# Receiver_VLC.net
KiCad netlist of a schematic drawn in Altium Designer
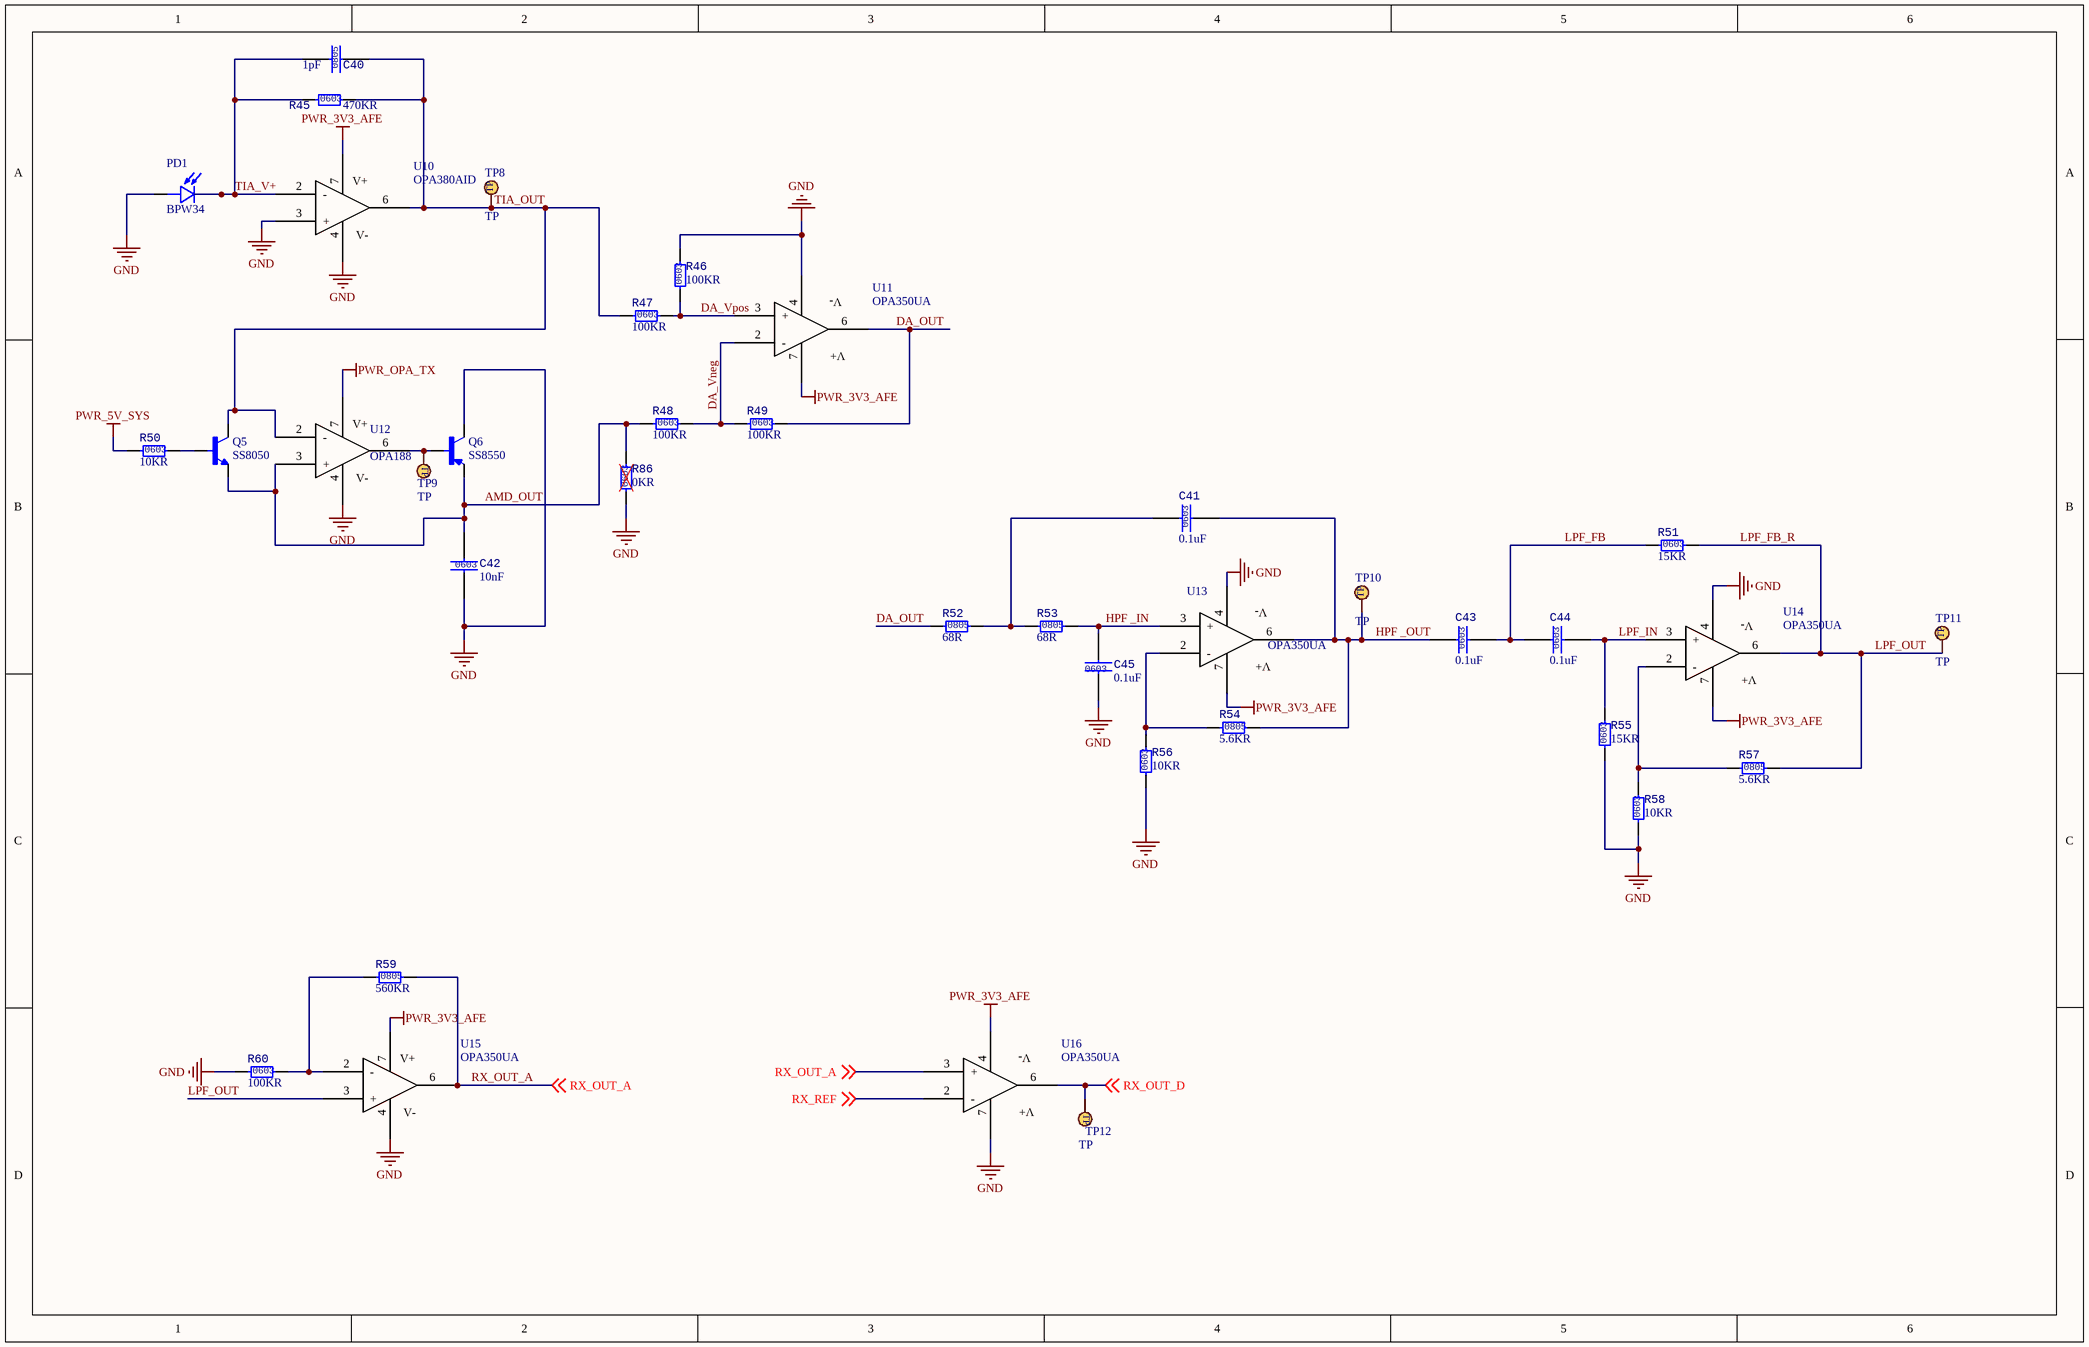
[diagram p0: Receiver_VLC.SchDoc]

(export (version "E")
  (design (tool "Eeschema 10.0.6"))
  (components
    (comp (ref "C40")
      (value "1pF")
      (footprint "CAPCER 0805 SMD")
      (fields (field (name "SIZE") "0805"))
      (libsource (lib "Database_Libs2") (part "CAPACITOR"))
    )
    (comp (ref "C41")
      (value "0.1uF")
      (footprint "CAPCER 0805 SMD")
      (description "CAPACITOR SMD 0.1uF 50V 10% 0603")
      (fields (field (name "SIZE") "0603") (field (name "TOLERANCE") "10%"))
      (libsource (lib "Database_Libs1") (part "CAPACITOR"))
    )
    (comp (ref "C42")
      (value "10nF")
      (footprint "CAPCER 0805 SMD")
      (description "CAPACITOR SMD 0.01uF 50V 10% 0603")
      (fields
        (field (name "SIZE") "0603")
        (field (name "TOLERANCE") "10%")
        (field (name "Comment") "Tụ Gốm 0603 10nF 50V")
      )
      (libsource (lib "Database_Libs1") (part "CAPACITOR"))
    )
    (comp (ref "C43")
      (value "0.1uF")
      (footprint "CAPCER 0805 SMD")
      (description "CAPACITOR SMD 0.1uF 50V 10% 0603")
      (fields (field (name "SIZE") "0603") (field (name "TOLERANCE") "10%"))
      (libsource (lib "Database_Libs1") (part "CAPACITOR"))
    )
    (comp (ref "C44")
      (value "0.1uF")
      (footprint "CAPCER 0805 SMD")
      (description "CAPACITOR SMD 0.1uF 50V 10% 0603")
      (fields (field (name "SIZE") "0603") (field (name "TOLERANCE") "10%"))
      (libsource (lib "Database_Libs1") (part "CAPACITOR"))
    )
    (comp (ref "C45")
      (value "0.1uF")
      (footprint "CAPCER 0805 SMD")
      (description "CAPACITOR SMD 0.1uF 50V 10% 0603")
      (fields (field (name "SIZE") "0603") (field (name "TOLERANCE") "10%"))
      (libsource (lib "Database_Libs1") (part "CAPACITOR"))
    )
    (comp (ref "PD1") (value "BPW34") (footprint "DIP-2") (libsource (lib "Database_Libs2") (part "PD")))
    (comp (ref "Q5")
      (value "SS8050")
      (footprint "SOT23-3")
      (description "SS8050 Y1 Transistor NPN 25V 1.5A 3 Chân SOT-23")
      (libsource (lib "Database_Libs2") (part "NPN"))
    )
    (comp (ref "Q6")
      (value "SS8550")
      (footprint "SOT23-3")
      (description "SS8550 Y2 Transistor PNP 25V 1.5A 3 Chân SOT-23")
      (libsource (lib "Database_Libs2") (part "PNP"))
    )
    (comp (ref "R45")
      (value "470KR")
      (footprint "RESC 0603(1608) SMD")
      (description "RESISTOR SMD 470KR OHM 1% 100mW 0603")
      (fields (field (name "SIZE") "0603") (field (name "TOLERANCE") "1%"))
      (libsource (lib "Database_Libs1") (part "RESISTOR"))
    )
    (comp (ref "R46")
      (value "100KR")
      (footprint "RESC 0603(1608) SMD")
      (description "RESISTOR SMD 100KR OHM 1% 100mW 0603")
      (fields (field (name "SIZE") "0603") (field (name "TOLERANCE") "1%"))
      (libsource (lib "") (part "RESISTOR_1"))
    )
    (comp (ref "R47")
      (value "100KR")
      (footprint "RESC 0603(1608) SMD")
      (description "RESISTOR SMD 100KR OHM 1% 100mW 0603")
      (fields (field (name "SIZE") "0603") (field (name "TOLERANCE") "1%"))
      (libsource (lib "Database_Libs1") (part "RESISTOR"))
    )
    (comp (ref "R48")
      (value "100KR")
      (footprint "RESC 0603(1608) SMD")
      (description "RESISTOR SMD 100KR OHM 1% 100mW 0603")
      (fields (field (name "SIZE") "0603") (field (name "TOLERANCE") "1%"))
      (libsource (lib "Database_Libs1") (part "RESISTOR"))
    )
    (comp (ref "R49")
      (value "100KR")
      (footprint "RESC 0603(1608) SMD")
      (description "RESISTOR SMD 100KR OHM 1% 100mW 0603")
      (fields (field (name "SIZE") "0603") (field (name "TOLERANCE") "1%"))
      (libsource (lib "Database_Libs1") (part "RESISTOR"))
    )
    (comp (ref "R50")
      (value "10KR")
      (footprint "RESC 0603(1608) SMD")
      (description "RESISTOR SMD 10KR OHM 1% 100mW 0603")
      (fields (field (name "SIZE") "0603") (field (name "TOLERANCE") "1%"))
      (libsource (lib "Database_Libs1") (part "RESISTOR"))
    )
    (comp (ref "R51")
      (value "15KR")
      (footprint "RESC 0603(1608) SMD")
      (fields (field (name "SIZE") "0603"))
      (libsource (lib "Database_Libs2") (part "RESISTOR"))
    )
    (comp (ref "R52")
      (value "68R")
      (footprint "RESC 0805 SMD")
      (description "Điện Trở 68 Ohm 0805 1%")
      (fields (field (name "SIZE") "0805"))
      (libsource (lib "Database_Libs2") (part "RESISTOR"))
    )
    (comp (ref "R53")
      (value "68R")
      (footprint "RESC 0805 SMD")
      (description "Điện Trở 68 Ohm 0805 1%")
      (fields (field (name "SIZE") "0805"))
      (libsource (lib "Database_Libs2") (part "RESISTOR"))
    )
    (comp (ref "R54")
      (value "5.6KR")
      (footprint "RESC 0805 SMD")
      (description "RESISTOR SMD 5.6KR OHM 1% 125mW 0805")
      (fields (field (name "SIZE") "0805") (field (name "TOLERANCE") "1%"))
      (libsource (lib "Database_Libs1") (part "RESISTOR"))
    )
    (comp (ref "R55")
      (value "15KR")
      (footprint "RESC 0603(1608) SMD")
      (fields (field (name "SIZE") "0603"))
      (libsource (lib "") (part "RESISTOR_1"))
    )
    (comp (ref "R56")
      (value "10KR")
      (footprint "RESC 0603(1608) SMD")
      (description "RESISTOR SMD 10KR OHM 1% 100mW 0603")
      (fields (field (name "SIZE") "0603") (field (name "TOLERANCE") "1%"))
      (libsource (lib "") (part "RESISTOR_1"))
    )
    (comp (ref "R57")
      (value "5.6KR")
      (footprint "RESC 0805 SMD")
      (description "RESISTOR SMD 5.6KR OHM 1% 125mW 0805")
      (fields (field (name "SIZE") "0805") (field (name "TOLERANCE") "1%"))
      (libsource (lib "Database_Libs1") (part "RESISTOR"))
    )
    (comp (ref "R58")
      (value "10KR")
      (footprint "RESC 0603(1608) SMD")
      (description "RESISTOR SMD 10KR OHM 1% 100mW 0603")
      (fields (field (name "SIZE") "0603") (field (name "TOLERANCE") "1%"))
      (libsource (lib "") (part "RESISTOR_1"))
    )
    (comp (ref "R59")
      (value "560KR")
      (footprint "RESC 0805 SMD")
      (fields (field (name "SIZE") "0805"))
      (libsource (lib "Database_Libs2") (part "RESISTOR"))
    )
    (comp (ref "R60")
      (value "100KR")
      (footprint "RESC 0603(1608) SMD")
      (description "RESISTOR SMD 100KR OHM 1% 100mW 0603")
      (fields (field (name "SIZE") "0603") (field (name "TOLERANCE") "1%"))
      (libsource (lib "Database_Libs1") (part "RESISTOR"))
    )
    (comp (ref "R86")
      (value "0KR")
      (footprint "RESC 0603(1608) SMD")
      (description "RESISTOR SMD 0KR OHM 1% 100mW 0603")
      (fields (field (name "SIZE") "0603") (field (name "TOLERANCE") "1%") (field (name "Comment") "0R-dni"))
      (libsource (lib "") (part "RESISTOR_1"))
    )
    (comp (ref "TP8")
      (value "TP")
      (footprint "TP_THT_1P0")
      (fields (field (name "Comment") "TEST POINT"))
      (libsource (lib "Database_Libs2") (part "Test_point"))
    )
    (comp (ref "TP9")
      (value "TP")
      (footprint "TP_THT_1P0")
      (fields (field (name "Comment") "TEST POINT"))
      (libsource (lib "Database_Libs2") (part "Test_point"))
    )
    (comp (ref "TP10")
      (value "TP")
      (footprint "TP_THT_1P0")
      (fields (field (name "Comment") "TEST POINT"))
      (libsource (lib "Database_Libs2") (part "Test_point"))
    )
    (comp (ref "TP11")
      (value "TP")
      (footprint "TP_THT_1P0")
      (fields (field (name "Comment") "TEST POINT"))
      (libsource (lib "Database_Libs2") (part "Test_point"))
    )
    (comp (ref "TP12")
      (value "TP")
      (footprint "TP_THT_1P0")
      (fields (field (name "Comment") "TEST POINT"))
      (libsource (lib "Database_Libs2") (part "Test_point"))
    )
    (comp (ref "U10")
      (value "OPA380AID")
      (footprint "8-SOIC-OPA")
      (libsource (lib "Database_Libs2") (part "OPA380AID"))
    )
    (comp (ref "U11")
      (value "OPA350UA")
      (footprint "8-SOIC-OPA")
      (libsource (lib "Database_Libs2") (part "OPA350UA"))
    )
    (comp (ref "U12")
      (value "OPA188")
      (footprint "8-SOIC-OPA")
      (description "Zero-Drift Amplifier 1 Circuit Rail-to-Rail 8-SOIC")
      (fields (field (name "Comment") "OPA188AID"))
      (libsource (lib "Database_Libs1") (part "OPA188AID"))
    )
    (comp (ref "U13")
      (value "OPA350UA")
      (footprint "8-SOIC-OPA")
      (libsource (lib "Database_Libs2") (part "OPA350UA"))
    )
    (comp (ref "U14")
      (value "OPA350UA")
      (footprint "8-SOIC-OPA")
      (libsource (lib "Database_Libs2") (part "OPA350UA"))
    )
    (comp (ref "U15")
      (value "OPA350UA")
      (footprint "8-SOIC-OPA")
      (libsource (lib "Database_Libs2") (part "OPA350UA"))
    )
    (comp (ref "U16")
      (value "OPA350UA")
      (footprint "8-SOIC-OPA")
      (libsource (lib "Database_Libs2") (part "OPA350UA"))
    )
  )
  (nets
    (net (code "1") (name "/AMD_OUT") (class "Default")
      (node (ref "C42") (pin "1") (pinfunction "1_1") (pintype "passive"))
      (node (ref "Q5") (pin "2") (pinfunction "E_2") (pintype "passive"))
      (node (ref "Q6") (pin "2") (pinfunction "E_2") (pintype "passive"))
      (node (ref "R48") (pin "1") (pinfunction "1_1") (pintype "passive"))
      (node (ref "R86") (pin "2") (pinfunction "2_2") (pintype "passive"))
      (node (ref "U12") (pin "3") (pinfunction "+_3") (pintype "passive"))
    )
    (net (code "2") (name "/DA_OUT") (class "Default")
      (node (ref "R49") (pin "2") (pinfunction "2_2") (pintype "passive"))
      (node (ref "R52") (pin "1") (pinfunction "1_1") (pintype "passive"))
      (node (ref "U11") (pin "6") (pinfunction "OUT_1_6") (pintype "passive"))
    )
    (net (code "3") (name "/DA_Vneg") (class "Default")
      (node (ref "R48") (pin "2") (pinfunction "2_2") (pintype "passive"))
      (node (ref "R49") (pin "1") (pinfunction "1_1") (pintype "passive"))
      (node (ref "U11") (pin "2") (pinfunction "-_2") (pintype "passive"))
    )
    (net (code "4") (name "/DA_Vpos") (class "Default")
      (node (ref "R46") (pin "1") (pinfunction "1_1") (pintype "passive"))
      (node (ref "R47") (pin "2") (pinfunction "2_2") (pintype "passive"))
      (node (ref "U11") (pin "3") (pinfunction "+_3") (pintype "passive"))
    )
    (net (code "5") (name "/HPF _IN") (class "Default")
      (node (ref "C45") (pin "2") (pinfunction "2_2") (pintype "passive"))
      (node (ref "R53") (pin "2") (pinfunction "2_2") (pintype "passive"))
      (node (ref "U13") (pin "3") (pinfunction "+_3") (pintype "passive"))
    )
    (net (code "6") (name "/HPF _OUT") (class "Default")
      (node (ref "C41") (pin "2") (pinfunction "2_2") (pintype "passive"))
      (node (ref "C43") (pin "1") (pinfunction "1_1") (pintype "passive"))
      (node (ref "R54") (pin "2") (pinfunction "2_2") (pintype "passive"))
      (node (ref "TP10") (pin "1") (pinfunction "1_1") (pintype "passive"))
      (node (ref "U13") (pin "6") (pinfunction "OUT_1_6") (pintype "passive"))
    )
    (net (code "7") (name "/LPF_FB") (class "Default")
      (node (ref "C43") (pin "2") (pinfunction "2_2") (pintype "passive"))
      (node (ref "C44") (pin "1") (pinfunction "1_1") (pintype "passive"))
      (node (ref "R51") (pin "1") (pinfunction "1_1") (pintype "passive"))
    )
    (net (code "8") (name "/LPF_FB_R") (class "Default")
      (node (ref "R51") (pin "2") (pinfunction "2_2") (pintype "passive"))
      (node (ref "R57") (pin "2") (pinfunction "2_2") (pintype "passive"))
      (node (ref "TP11") (pin "1") (pinfunction "1_1") (pintype "passive"))
      (node (ref "U14") (pin "6") (pinfunction "OUT_1_6") (pintype "passive"))
      (node (ref "U15") (pin "3") (pinfunction "+_3") (pintype "passive"))
    )
    (net (code "9") (name "/LPF_IN") (class "Default")
      (node (ref "C44") (pin "2") (pinfunction "2_2") (pintype "passive"))
      (node (ref "R55") (pin "2") (pinfunction "2_2") (pintype "passive"))
      (node (ref "U14") (pin "3") (pinfunction "+_3") (pintype "passive"))
    )
    (net (code "10") (name "/TIA_OUT") (class "Default")
      (node (ref "C40") (pin "2") (pinfunction "2_2") (pintype "passive"))
      (node (ref "Q5") (pin "3") (pinfunction "C_3") (pintype "passive"))
      (node (ref "R45") (pin "2") (pinfunction "2_2") (pintype "passive"))
      (node (ref "R47") (pin "1") (pinfunction "1_1") (pintype "passive"))
      (node (ref "TP8") (pin "1") (pinfunction "1_1") (pintype "passive"))
      (node (ref "U10") (pin "6") (pinfunction "OUT_1_6") (pintype "passive"))
      (node (ref "U12") (pin "2") (pinfunction "-_2") (pintype "passive"))
    )
    (net (code "11") (name "/TIA_V+") (class "Default")
      (node (ref "C40") (pin "1") (pinfunction "1_1") (pintype "passive"))
      (node (ref "PD1") (pin "C") (pinfunction "C_C") (pintype "passive"))
      (node (ref "R45") (pin "1") (pinfunction "1_1") (pintype "passive"))
      (node (ref "U10") (pin "2") (pinfunction "-_2") (pintype "passive"))
    )
    (net (code "12") (name "GND") (class "Default")
      (node (ref "C42") (pin "2") (pinfunction "2_2") (pintype "passive"))
      (node (ref "C45") (pin "1") (pinfunction "1_1") (pintype "passive"))
      (node (ref "PD1") (pin "A") (pinfunction "A_A") (pintype "passive"))
      (node (ref "Q6") (pin "3") (pinfunction "C_3") (pintype "passive"))
      (node (ref "R46") (pin "2") (pinfunction "2_2") (pintype "passive"))
      (node (ref "R55") (pin "1") (pinfunction "1_1") (pintype "passive"))
      (node (ref "R56") (pin "1") (pinfunction "1_1") (pintype "passive"))
      (node (ref "R58") (pin "1") (pinfunction "1_1") (pintype "passive"))
      (node (ref "R60") (pin "1") (pinfunction "1_1") (pintype "passive"))
      (node (ref "R86") (pin "1") (pinfunction "1_1") (pintype "passive"))
      (node (ref "U10") (pin "3") (pinfunction "+_3") (pintype "passive"))
      (node (ref "U10") (pin "4") (pinfunction "GND_4") (pintype "passive"))
      (node (ref "U11") (pin "4") (pinfunction "GND_4") (pintype "passive"))
      (node (ref "U12") (pin "4") (pinfunction "GND_4") (pintype "passive"))
      (node (ref "U13") (pin "4") (pinfunction "GND_4") (pintype "passive"))
      (node (ref "U14") (pin "4") (pinfunction "GND_4") (pintype "passive"))
      (node (ref "U15") (pin "4") (pinfunction "GND_4") (pintype "passive"))
      (node (ref "U16") (pin "7") (pinfunction "VCC_7") (pintype "passive"))
    )
    (net (code "13") (name "Net-(C41-Pad1)") (class "Default")
      (node (ref "C41") (pin "1") (pinfunction "1_1") (pintype "passive"))
      (node (ref "R52") (pin "2") (pinfunction "2_2") (pintype "passive"))
      (node (ref "R53") (pin "1") (pinfunction "1_1") (pintype "passive"))
    )
    (net (code "14") (name "Net-(Q5-B)") (class "Default")
      (node (ref "Q5") (pin "1") (pinfunction "B_1") (pintype "passive"))
      (node (ref "R50") (pin "2") (pinfunction "2_2") (pintype "passive"))
    )
    (net (code "15") (name "Net-(Q6-B)") (class "Default")
      (node (ref "Q6") (pin "1") (pinfunction "B_1") (pintype "passive"))
      (node (ref "TP9") (pin "1") (pinfunction "1_1") (pintype "passive"))
      (node (ref "U12") (pin "6") (pinfunction "OUT_1_6") (pintype "passive"))
    )
    (net (code "16") (name "Net-(U13--)") (class "Default")
      (node (ref "R54") (pin "1") (pinfunction "1_1") (pintype "passive"))
      (node (ref "R56") (pin "2") (pinfunction "2_2") (pintype "passive"))
      (node (ref "U13") (pin "2") (pinfunction "-_2") (pintype "passive"))
    )
    (net (code "17") (name "Net-(U14--)") (class "Default")
      (node (ref "R57") (pin "1") (pinfunction "1_1") (pintype "passive"))
      (node (ref "R58") (pin "2") (pinfunction "2_2") (pintype "passive"))
      (node (ref "U14") (pin "2") (pinfunction "-_2") (pintype "passive"))
    )
    (net (code "18") (name "Net-(U15--)") (class "Default")
      (node (ref "R59") (pin "1") (pinfunction "1_1") (pintype "passive"))
      (node (ref "R60") (pin "2") (pinfunction "2_2") (pintype "passive"))
      (node (ref "U15") (pin "2") (pinfunction "-_2") (pintype "passive"))
    )
    (net (code "19") (name "PWR_3V3_AFE") (class "Default")
      (node (ref "U10") (pin "7") (pinfunction "VCC_7") (pintype "passive"))
      (node (ref "U11") (pin "7") (pinfunction "VCC_7") (pintype "passive"))
      (node (ref "U13") (pin "7") (pinfunction "VCC_7") (pintype "passive"))
      (node (ref "U14") (pin "7") (pinfunction "VCC_7") (pintype "passive"))
      (node (ref "U15") (pin "7") (pinfunction "VCC_7") (pintype "passive"))
      (node (ref "U16") (pin "4") (pinfunction "GND_4") (pintype "passive"))
    )
    (net (code "20") (name "PWR_5V_SYS") (class "Default")
      (node (ref "R50") (pin "1") (pinfunction "1_1") (pintype "passive"))
    )
    (net (code "21") (name "PWR_OPA_TX") (class "Default")
      (node (ref "U12") (pin "7") (pinfunction "VCC_7") (pintype "passive"))
    )
    (net (code "22") (name "RX_OUT_A") (class "Default")
      (node (ref "R59") (pin "2") (pinfunction "2_2") (pintype "passive"))
      (node (ref "U15") (pin "6") (pinfunction "OUT_1_6") (pintype "passive"))
      (node (ref "U16") (pin "3") (pinfunction "+_3") (pintype "passive"))
    )
    (net (code "23") (name "RX_OUT_D") (class "Default")
      (node (ref "TP12") (pin "1") (pinfunction "1_1") (pintype "passive"))
      (node (ref "U16") (pin "6") (pinfunction "OUT_1_6") (pintype "passive"))
    )
    (net (code "24") (name "RX_REF") (class "Default")
      (node (ref "U16") (pin "2") (pinfunction "-_2") (pintype "passive"))
    )
  )
)
